# CURRENT_SOURCE.net
KiCad netlist of a schematic drawn in Altium Designer
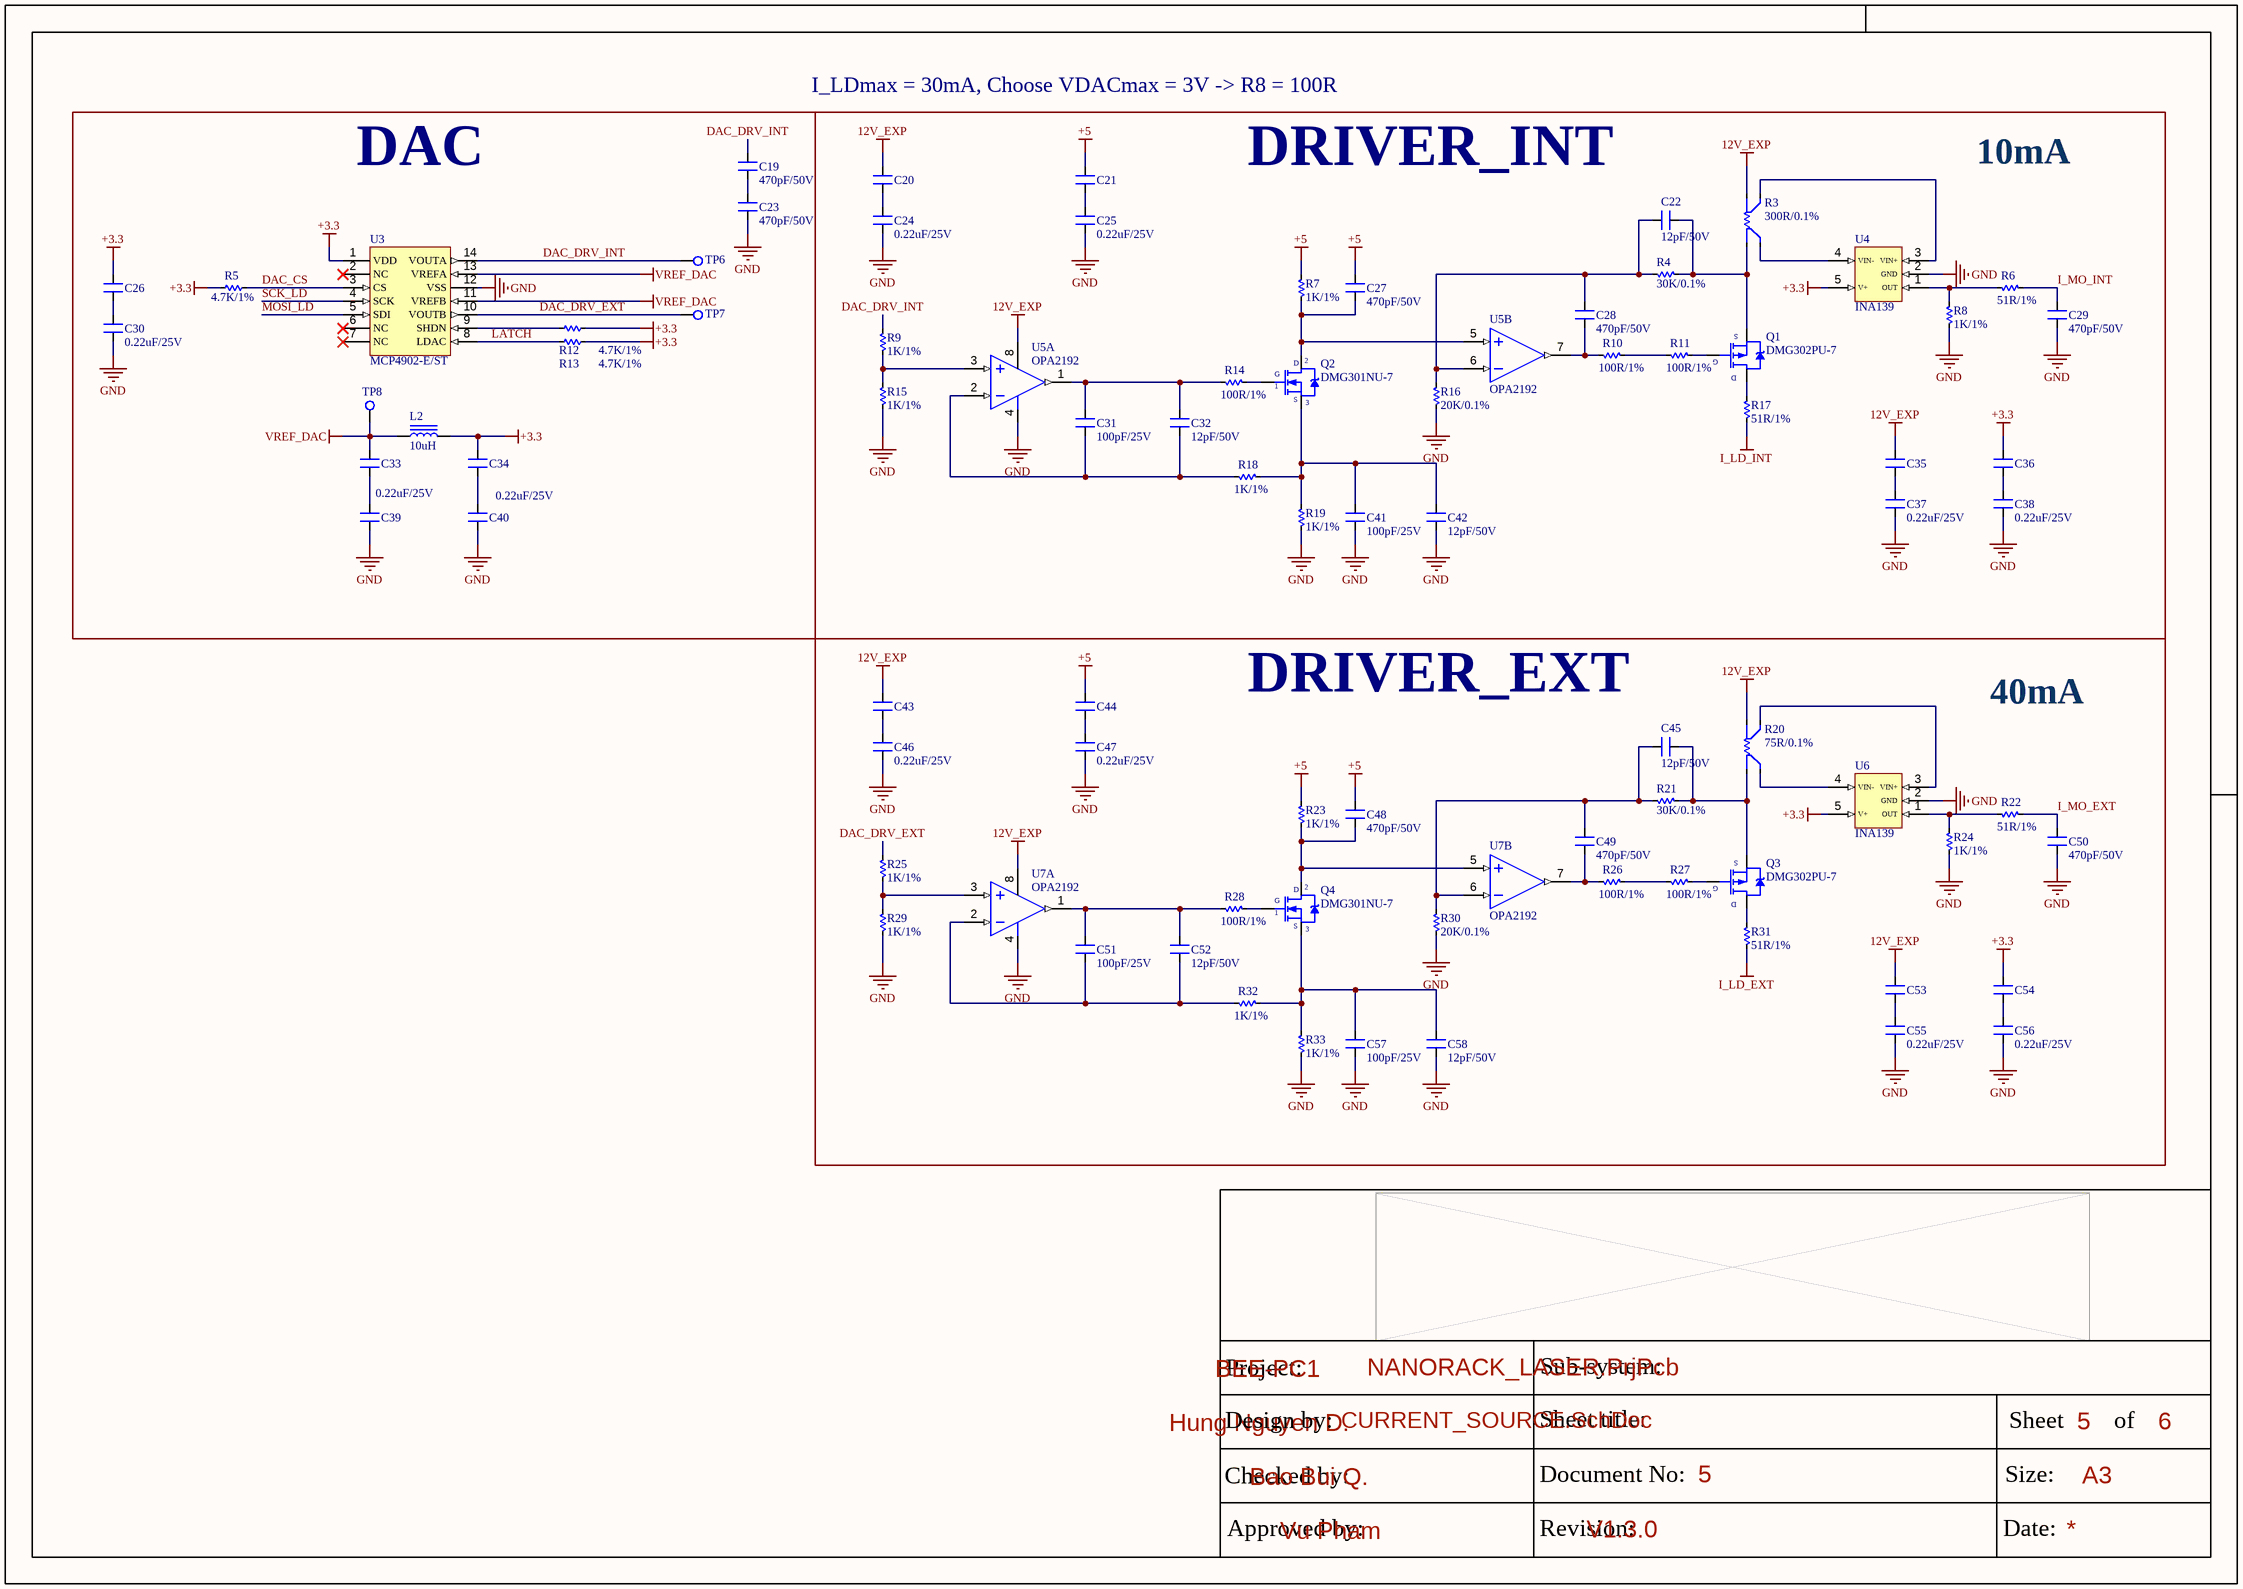
[diagram p0: CURRENT_SOURCE.SchDoc]

(export (version "E")
  (design (tool "Eeschema 10.0.6"))
  (components
    (comp (ref "C19")
      (value "470pF/50V")
      (footprint "SM-0603")
      (description "CL10B471KB8NNNC")
      (libsource (lib "Capacitors") (part "CM"))
    )
    (comp (ref "C20")
      (value "0.22uF/25V")
      (footprint "SM-0603")
      (description "CL10B224KA8NNNC")
      (libsource (lib "Capacitors") (part "CM"))
    )
    (comp (ref "C21")
      (value "0.22uF/25V")
      (footprint "SM-0603")
      (description "CL10B224KA8NNNC")
      (libsource (lib "Capacitors") (part "CM"))
    )
    (comp (ref "C22")
      (value "12pF/50V")
      (footprint "SM-0603")
      (description "CL10C120JB81PNC")
      (libsource (lib "Capacitors") (part "CM"))
    )
    (comp (ref "C23")
      (value "470pF/50V")
      (footprint "SM-0603")
      (description "CL10B471KB8NNNC")
      (libsource (lib "Capacitors") (part "CM"))
    )
    (comp (ref "C24")
      (value "0.22uF/25V")
      (footprint "SM-0603")
      (description "CL10B224KA8NNNC")
      (libsource (lib "Capacitors") (part "CM"))
    )
    (comp (ref "C25")
      (value "0.22uF/25V")
      (footprint "SM-0603")
      (description "CL10B224KA8NNNC")
      (libsource (lib "Capacitors") (part "CM"))
    )
    (comp (ref "C26")
      (value "0.22uF/25V")
      (footprint "SM-0603")
      (description "CL10B224KA8NNNC")
      (libsource (lib "Capacitors") (part "CM"))
    )
    (comp (ref "C27")
      (value "470pF/50V")
      (footprint "SM-0603")
      (description "CL10B471KB8NNNC")
      (libsource (lib "Capacitors") (part "CM"))
    )
    (comp (ref "C28")
      (value "470pF/50V")
      (footprint "SM-0603")
      (description "CL10B471KB8NNNC")
      (libsource (lib "Capacitors") (part "CM"))
    )
    (comp (ref "C29")
      (value "470pF/50V")
      (footprint "SM-0603")
      (description "CL10B471KB8NNNC")
      (libsource (lib "Capacitors") (part "CM"))
    )
    (comp (ref "C30")
      (value "0.22uF/25V")
      (footprint "SM-0603")
      (description "CL10B224KA8NNNC")
      (libsource (lib "Capacitors") (part "CM"))
    )
    (comp (ref "C31")
      (value "100pF/25V")
      (footprint "SM-0603")
      (description "C0603C101M3HACTU")
      (libsource (lib "Capacitors") (part "CM"))
    )
    (comp (ref "C32")
      (value "12pF/50V")
      (footprint "SM-0603")
      (description "CL10C120JB81PNC")
      (libsource (lib "Capacitors") (part "CM"))
    )
    (comp (ref "C33")
      (value "0.22uF/25V")
      (footprint "SM-0603")
      (description "CL10B224KA8NNNC")
      (libsource (lib "Capacitors") (part "CM"))
    )
    (comp (ref "C34")
      (value "0.22uF/25V")
      (footprint "SM-0603")
      (description "CL10B224KA8NNNC")
      (libsource (lib "Capacitors") (part "CM"))
    )
    (comp (ref "C35")
      (value "0.22uF/25V")
      (footprint "SM-0603")
      (description "CL10B224KA8NNNC")
      (libsource (lib "Capacitors") (part "CM"))
    )
    (comp (ref "C36")
      (value "0.22uF/25V")
      (footprint "SM-0603")
      (description "CL10B224KA8NNNC")
      (libsource (lib "Capacitors") (part "CM"))
    )
    (comp (ref "C37")
      (value "0.22uF/25V")
      (footprint "SM-0603")
      (description "CL10B224KA8NNNC")
      (libsource (lib "Capacitors") (part "CM"))
    )
    (comp (ref "C38")
      (value "0.22uF/25V")
      (footprint "SM-0603")
      (description "CL10B224KA8NNNC")
      (libsource (lib "Capacitors") (part "CM"))
    )
    (comp (ref "C39")
      (value "0.22uF/25V")
      (footprint "SM-0603")
      (description "CL10B224KA8NNNC")
      (libsource (lib "Capacitors") (part "CM"))
    )
    (comp (ref "C40")
      (value "0.22uF/25V")
      (footprint "SM-0603")
      (description "CL10B224KA8NNNC")
      (libsource (lib "Capacitors") (part "CM"))
    )
    (comp (ref "C41")
      (value "100pF/25V")
      (footprint "SM-0603")
      (description "C0603C101M3HACTU")
      (libsource (lib "Capacitors") (part "CM"))
    )
    (comp (ref "C42")
      (value "12pF/50V")
      (footprint "SM-0603")
      (description "CL10C120JB81PNC")
      (libsource (lib "Capacitors") (part "CM"))
    )
    (comp (ref "C43")
      (value "0.22uF/25V")
      (footprint "SM-0603")
      (description "CL10B224KA8NNNC")
      (libsource (lib "Capacitors") (part "CM"))
    )
    (comp (ref "C44")
      (value "0.22uF/25V")
      (footprint "SM-0603")
      (description "CL10B224KA8NNNC")
      (libsource (lib "Capacitors") (part "CM"))
    )
    (comp (ref "C45")
      (value "12pF/50V")
      (footprint "SM-0603")
      (description "CL10C120JB81PNC")
      (libsource (lib "Capacitors") (part "CM"))
    )
    (comp (ref "C46")
      (value "0.22uF/25V")
      (footprint "SM-0603")
      (description "CL10B224KA8NNNC")
      (libsource (lib "Capacitors") (part "CM"))
    )
    (comp (ref "C47")
      (value "0.22uF/25V")
      (footprint "SM-0603")
      (description "CL10B224KA8NNNC")
      (libsource (lib "Capacitors") (part "CM"))
    )
    (comp (ref "C48")
      (value "470pF/50V")
      (footprint "SM-0603")
      (description "CL10B471KB8NNNC")
      (libsource (lib "Capacitors") (part "CM"))
    )
    (comp (ref "C49")
      (value "470pF/50V")
      (footprint "SM-0603")
      (description "CL10B471KB8NNNC")
      (libsource (lib "Capacitors") (part "CM"))
    )
    (comp (ref "C50")
      (value "470pF/50V")
      (footprint "SM-0603")
      (description "CL10B471KB8NNNC")
      (libsource (lib "Capacitors") (part "CM"))
    )
    (comp (ref "C51")
      (value "100pF/25V")
      (footprint "SM-0603")
      (description "C0603C101M3HACTU")
      (libsource (lib "Capacitors") (part "CM"))
    )
    (comp (ref "C52")
      (value "12pF/50V")
      (footprint "SM-0603")
      (description "CL10C120JB81PNC")
      (libsource (lib "Capacitors") (part "CM"))
    )
    (comp (ref "C53")
      (value "0.22uF/25V")
      (footprint "SM-0603")
      (description "CL10B224KA8NNNC")
      (libsource (lib "Capacitors") (part "CM"))
    )
    (comp (ref "C54")
      (value "0.22uF/25V")
      (footprint "SM-0603")
      (description "CL10B224KA8NNNC")
      (libsource (lib "Capacitors") (part "CM"))
    )
    (comp (ref "C55")
      (value "0.22uF/25V")
      (footprint "SM-0603")
      (description "CL10B224KA8NNNC")
      (libsource (lib "Capacitors") (part "CM"))
    )
    (comp (ref "C56")
      (value "0.22uF/25V")
      (footprint "SM-0603")
      (description "CL10B224KA8NNNC")
      (libsource (lib "Capacitors") (part "CM"))
    )
    (comp (ref "C57")
      (value "100pF/25V")
      (footprint "SM-0603")
      (description "C0603C101M3HACTU")
      (libsource (lib "Capacitors") (part "CM"))
    )
    (comp (ref "C58")
      (value "12pF/50V")
      (footprint "SM-0603")
      (description "CL10C120JB81PNC")
      (libsource (lib "Capacitors") (part "CM"))
    )
    (comp (ref "L2")
      (value "10uH")
      (footprint "FER 0805/2012")
      (description "MLZ1608N100LT000")
      (libsource (lib "INDUCTOR") (part "Inductor"))
    )
    (comp (ref "Q1")
      (value "DMG302PU-7")
      (footprint "SOT23-3-132")
      (libsource (lib "DAK_Altium_Integrated_Lib") (part "P_MOSFET"))
    )
    (comp (ref "Q2")
      (value "DMG301NU-7")
      (footprint "SOT23-3-132")
      (libsource (lib "DAK_Altium_Integrated_Lib") (part "N_MOSFET"))
    )
    (comp (ref "Q3")
      (value "DMG302PU-7")
      (footprint "SOT23-3-132")
      (libsource (lib "DAK_Altium_Integrated_Lib") (part "P_MOSFET"))
    )
    (comp (ref "Q4")
      (value "DMG301NU-7")
      (footprint "SOT23-3-132")
      (libsource (lib "DAK_Altium_Integrated_Lib") (part "N_MOSFET"))
    )
    (comp (ref "R3")
      (value "300R/0.1%")
      (footprint "RES_SMD_0603_SHUNT")
      (description "RT0603BRC07300RL")
      (libsource (lib "DAK_Altium_Integrated_Lib") (part "RES_SMD_SHUNT"))
    )
    (comp (ref "R4")
      (value "30K/0.1%")
      (footprint "RES-SMD-0603")
      (description "ERA-3AEB303V")
      (fields
        (field (name "MANUFACTURER") "Generic Components")
        (field (name "PUBLISHER") "Altium Hobart Technology Centre")
      )
      (libsource (lib "Library") (part "Res-SMD"))
    )
    (comp (ref "R5")
      (value "4.7K/1%")
      (footprint "RES-SMD-0603")
      (description "ERJ-3EKF4701V")
      (fields
        (field (name "MANUFACTURER") "Generic Components")
        (field (name "PUBLISHER") "Altium Hobart Technology Centre")
      )
      (libsource (lib "Library") (part "Res-SMD"))
    )
    (comp (ref "R6")
      (value "51R/1%")
      (footprint "RES-SMD-0603")
      (description "ERJ-3EKF51R0V")
      (fields
        (field (name "MANUFACTURER") "Generic Components")
        (field (name "PUBLISHER") "Altium Hobart Technology Centre")
      )
      (libsource (lib "Library") (part "Res-SMD"))
    )
    (comp (ref "R7")
      (value "1K/1%")
      (footprint "RES-SMD-0603")
      (description "ERJ-3EKF1001V")
      (fields
        (field (name "MANUFACTURER") "Generic Components")
        (field (name "PUBLISHER") "Altium Hobart Technology Centre")
      )
      (libsource (lib "Library") (part "Res-SMD"))
    )
    (comp (ref "R8")
      (value "1K/1%")
      (footprint "RES-SMD-0603")
      (description "ERJ-3EKF1001V")
      (fields
        (field (name "MANUFACTURER") "Generic Components")
        (field (name "PUBLISHER") "Altium Hobart Technology Centre")
      )
      (libsource (lib "Library") (part "Res-SMD"))
    )
    (comp (ref "R9")
      (value "1K/1%")
      (footprint "RES-SMD-0603")
      (description "ERJ-3EKF1001V")
      (fields
        (field (name "MANUFACTURER") "Generic Components")
        (field (name "PUBLISHER") "Altium Hobart Technology Centre")
      )
      (libsource (lib "Library") (part "Res-SMD"))
    )
    (comp (ref "R10")
      (value "100R/1%")
      (footprint "RES-SMD-0603")
      (description "ERJ-PA3D1000V")
      (fields
        (field (name "MANUFACTURER") "Generic Components")
        (field (name "PUBLISHER") "Altium Hobart Technology Centre")
      )
      (libsource (lib "Library") (part "Res-SMD"))
    )
    (comp (ref "R11")
      (value "100R/1%")
      (footprint "RES-SMD-0603")
      (description "ERJ-PA3D1000V")
      (fields
        (field (name "MANUFACTURER") "Generic Components")
        (field (name "PUBLISHER") "Altium Hobart Technology Centre")
      )
      (libsource (lib "Library") (part "Res-SMD"))
    )
    (comp (ref "R12")
      (value "4.7K/1%")
      (footprint "RES-SMD-0603")
      (description "ERJ-3EKF4701V")
      (fields
        (field (name "MANUFACTURER") "Generic Components")
        (field (name "PUBLISHER") "Altium Hobart Technology Centre")
      )
      (libsource (lib "Library") (part "Res-SMD"))
    )
    (comp (ref "R13")
      (value "4.7K/1%")
      (footprint "RES-SMD-0603")
      (description "ERJ-3EKF4701V")
      (fields
        (field (name "MANUFACTURER") "Generic Components")
        (field (name "PUBLISHER") "Altium Hobart Technology Centre")
      )
      (libsource (lib "Library") (part "Res-SMD"))
    )
    (comp (ref "R14")
      (value "100R/1%")
      (footprint "RES-SMD-0603")
      (description "ERJ-PA3D1000V")
      (fields
        (field (name "MANUFACTURER") "Generic Components")
        (field (name "PUBLISHER") "Altium Hobart Technology Centre")
      )
      (libsource (lib "Library") (part "Res-SMD"))
    )
    (comp (ref "R15")
      (value "1K/1%")
      (footprint "RES-SMD-0603")
      (description "ERJ-3EKF1001V")
      (fields
        (field (name "MANUFACTURER") "Generic Components")
        (field (name "PUBLISHER") "Altium Hobart Technology Centre")
      )
      (libsource (lib "Library") (part "Res-SMD"))
    )
    (comp (ref "R16")
      (value "20K/0.1%")
      (footprint "RES-SMD-0603")
      (description "ERA-3AEB203V")
      (fields
        (field (name "MANUFACTURER") "Generic Components")
        (field (name "PUBLISHER") "Altium Hobart Technology Centre")
      )
      (libsource (lib "Library") (part "Res-SMD"))
    )
    (comp (ref "R17")
      (value "51R/1%")
      (footprint "RES-SMD-0603")
      (description "ERJ-3EKF51R0V")
      (fields
        (field (name "MANUFACTURER") "Generic Components")
        (field (name "PUBLISHER") "Altium Hobart Technology Centre")
      )
      (libsource (lib "Library") (part "Res-SMD"))
    )
    (comp (ref "R18")
      (value "1K/1%")
      (footprint "RES-SMD-0603")
      (description "ERJ-3EKF1001V")
      (fields
        (field (name "MANUFACTURER") "Generic Components")
        (field (name "PUBLISHER") "Altium Hobart Technology Centre")
      )
      (libsource (lib "Library") (part "Res-SMD"))
    )
    (comp (ref "R19")
      (value "1K/1%")
      (footprint "RES-SMD-0603")
      (description "ERJ-3EKF1001V")
      (fields
        (field (name "MANUFACTURER") "Generic Components")
        (field (name "PUBLISHER") "Altium Hobart Technology Centre")
      )
      (libsource (lib "Library") (part "Res-SMD"))
    )
    (comp (ref "R20")
      (value "75R/0.1%")
      (footprint "RES_SMD_0603_SHUNT")
      (description "TNPW060375R0BEEA")
      (libsource (lib "DAK_Altium_Integrated_Lib") (part "RES_SMD_SHUNT"))
    )
    (comp (ref "R21")
      (value "30K/0.1%")
      (footprint "RES-SMD-0603")
      (description "ERA-3AEB303V")
      (fields
        (field (name "MANUFACTURER") "Generic Components")
        (field (name "PUBLISHER") "Altium Hobart Technology Centre")
      )
      (libsource (lib "Library") (part "Res-SMD"))
    )
    (comp (ref "R22")
      (value "51R/1%")
      (footprint "RES-SMD-0603")
      (description "ERJ-3EKF51R0V")
      (fields
        (field (name "MANUFACTURER") "Generic Components")
        (field (name "PUBLISHER") "Altium Hobart Technology Centre")
      )
      (libsource (lib "Library") (part "Res-SMD"))
    )
    (comp (ref "R23")
      (value "1K/1%")
      (footprint "RES-SMD-0603")
      (description "ERJ-3EKF1001V")
      (fields
        (field (name "MANUFACTURER") "Generic Components")
        (field (name "PUBLISHER") "Altium Hobart Technology Centre")
      )
      (libsource (lib "Library") (part "Res-SMD"))
    )
    (comp (ref "R24")
      (value "1K/1%")
      (footprint "RES-SMD-0603")
      (description "ERJ-3EKF1001V")
      (fields
        (field (name "MANUFACTURER") "Generic Components")
        (field (name "PUBLISHER") "Altium Hobart Technology Centre")
      )
      (libsource (lib "Library") (part "Res-SMD"))
    )
    (comp (ref "R25")
      (value "1K/1%")
      (footprint "RES-SMD-0603")
      (description "ERJ-3EKF1001V")
      (fields
        (field (name "MANUFACTURER") "Generic Components")
        (field (name "PUBLISHER") "Altium Hobart Technology Centre")
      )
      (libsource (lib "Library") (part "Res-SMD"))
    )
    (comp (ref "R26")
      (value "100R/1%")
      (footprint "RES-SMD-0603")
      (description "ERJ-PA3D1000V")
      (fields
        (field (name "MANUFACTURER") "Generic Components")
        (field (name "PUBLISHER") "Altium Hobart Technology Centre")
      )
      (libsource (lib "Library") (part "Res-SMD"))
    )
    (comp (ref "R27")
      (value "100R/1%")
      (footprint "RES-SMD-0603")
      (description "ERJ-PA3D1000V")
      (fields
        (field (name "MANUFACTURER") "Generic Components")
        (field (name "PUBLISHER") "Altium Hobart Technology Centre")
      )
      (libsource (lib "Library") (part "Res-SMD"))
    )
    (comp (ref "R28")
      (value "100R/1%")
      (footprint "RES-SMD-0603")
      (description "ERJ-PA3D1000V")
      (fields
        (field (name "MANUFACTURER") "Generic Components")
        (field (name "PUBLISHER") "Altium Hobart Technology Centre")
      )
      (libsource (lib "Library") (part "Res-SMD"))
    )
    (comp (ref "R29")
      (value "1K/1%")
      (footprint "RES-SMD-0603")
      (description "ERJ-3EKF1001V")
      (fields
        (field (name "MANUFACTURER") "Generic Components")
        (field (name "PUBLISHER") "Altium Hobart Technology Centre")
      )
      (libsource (lib "Library") (part "Res-SMD"))
    )
    (comp (ref "R30")
      (value "20K/0.1%")
      (footprint "RES-SMD-0603")
      (description "ERA-3AEB203V")
      (fields
        (field (name "MANUFACTURER") "Generic Components")
        (field (name "PUBLISHER") "Altium Hobart Technology Centre")
      )
      (libsource (lib "Library") (part "Res-SMD"))
    )
    (comp (ref "R31")
      (value "51R/1%")
      (footprint "RES-SMD-0603")
      (description "ERJ-3EKF51R0V")
      (fields
        (field (name "MANUFACTURER") "Generic Components")
        (field (name "PUBLISHER") "Altium Hobart Technology Centre")
      )
      (libsource (lib "Library") (part "Res-SMD"))
    )
    (comp (ref "R32")
      (value "1K/1%")
      (footprint "RES-SMD-0603")
      (description "ERJ-3EKF1001V")
      (fields
        (field (name "MANUFACTURER") "Generic Components")
        (field (name "PUBLISHER") "Altium Hobart Technology Centre")
      )
      (libsource (lib "Library") (part "Res-SMD"))
    )
    (comp (ref "R33")
      (value "1K/1%")
      (footprint "RES-SMD-0603")
      (description "ERJ-3EKF1001V")
      (fields
        (field (name "MANUFACTURER") "Generic Components")
        (field (name "PUBLISHER") "Altium Hobart Technology Centre")
      )
      (libsource (lib "Library") (part "Res-SMD"))
    )
    (comp (ref "TP6")
      (value "Test_Point")
      (footprint "TESTPOINT")
      (libsource (lib "Library_HUNG") (part "Test_Point"))
    )
    (comp (ref "TP7")
      (value "Test_Point")
      (footprint "TESTPOINT")
      (libsource (lib "Library_HUNG") (part "Test_Point"))
    )
    (comp (ref "TP8")
      (value "Test_Point")
      (footprint "TESTPOINT")
      (libsource (lib "Library_HUNG") (part "Test_Point"))
    )
    (comp (ref "U3")
      (value "MCP4902-E/ST")
      (footprint "TSSOP14")
      (libsource (lib "Library") (part "MCP4902"))
    )
    (comp (ref "U4")
      (value "INA139")
      (footprint "SOT23-5")
      (description "INA139NA/250")
      (libsource (lib "Library_HUNG") (part "INA139"))
    )
    (comp (ref "U5")
      (value "OPA2192")
      (footprint "SO8")
      (description "OPA2192IDR")
      (libsource (lib "Library") (part "LM358"))
    )
    (comp (ref "U6")
      (value "INA139")
      (footprint "SOT23-5")
      (description "INA139NA/250")
      (libsource (lib "Library_HUNG") (part "INA139"))
    )
    (comp (ref "U7")
      (value "OPA2192")
      (footprint "SO8")
      (description "OPA2192IDR")
      (libsource (lib "Library") (part "LM358"))
    )
  )
  (nets
    (net (code "1") (name "+3.3") (class "Default")
      (node (ref "C26") (pin "2") (pinfunction "2_2") (pintype "passive"))
      (node (ref "C34") (pin "2") (pinfunction "2_2") (pintype "passive"))
      (node (ref "C36") (pin "2") (pinfunction "2_2") (pintype "passive"))
      (node (ref "C54") (pin "2") (pinfunction "2_2") (pintype "passive"))
      (node (ref "L2") (pin "2") (pinfunction "2_2") (pintype "passive"))
      (node (ref "R12") (pin "1") (pinfunction "1_1") (pintype "passive"))
      (node (ref "R13") (pin "1") (pinfunction "1_1") (pintype "passive"))
      (node (ref "R5") (pin "2") (pinfunction "2_2") (pintype "passive"))
      (node (ref "U3") (pin "1") (pinfunction "VDD_1") (pintype "power_in"))
      (node (ref "U4") (pin "5") (pinfunction "V+_5") (pintype "input"))
      (node (ref "U6") (pin "5") (pinfunction "V+_5") (pintype "input"))
    )
    (net (code "2") (name "+5") (class "Default")
      (node (ref "C21") (pin "2") (pinfunction "2_2") (pintype "passive"))
      (node (ref "C27") (pin "2") (pinfunction "2_2") (pintype "passive"))
      (node (ref "C44") (pin "2") (pinfunction "2_2") (pintype "passive"))
      (node (ref "C48") (pin "2") (pinfunction "2_2") (pintype "passive"))
      (node (ref "R23") (pin "2") (pinfunction "2_2") (pintype "passive"))
      (node (ref "R7") (pin "2") (pinfunction "2_2") (pintype "passive"))
    )
    (net (code "3") (name "/DAC_CS") (class "Default")
      (node (ref "R5") (pin "1") (pinfunction "1_1") (pintype "passive"))
      (node (ref "U3") (pin "3") (pinfunction "CS_3") (pintype "input"))
    )
    (net (code "4") (name "/DAC_DRV_EXT") (class "Default")
      (node (ref "R25") (pin "2") (pinfunction "2_2") (pintype "passive"))
      (node (ref "TP7") (pin "1") (pintype "power_in"))
      (node (ref "U3") (pin "10") (pinfunction "VOUTB_10") (pintype "output"))
    )
    (net (code "5") (name "/DAC_DRV_INT") (class "Default")
      (node (ref "C19") (pin "2") (pinfunction "2_2") (pintype "passive"))
      (node (ref "R9") (pin "2") (pinfunction "2_2") (pintype "passive"))
      (node (ref "TP6") (pin "1") (pintype "power_in"))
      (node (ref "U3") (pin "14") (pinfunction "VOUTA_14") (pintype "output"))
    )
    (net (code "6") (name "/I_MO_EXT") (class "Default")
      (node (ref "C50") (pin "2") (pinfunction "2_2") (pintype "passive"))
      (node (ref "R22") (pin "2") (pinfunction "2_2") (pintype "passive"))
    )
    (net (code "7") (name "/I_MO_INT") (class "Default")
      (node (ref "C29") (pin "2") (pinfunction "2_2") (pintype "passive"))
      (node (ref "R6") (pin "2") (pinfunction "2_2") (pintype "passive"))
    )
    (net (code "8") (name "/LATCH") (class "Default")
      (node (ref "R13") (pin "2") (pinfunction "2_2") (pintype "passive"))
      (node (ref "U3") (pin "8") (pinfunction "LDAC_8") (pintype "input"))
    )
    (net (code "9") (name "/MOSI_LD") (class "Default")
      (node (ref "U3") (pin "5") (pinfunction "SDI_5") (pintype "input"))
    )
    (net (code "10") (name "/SCK_LD") (class "Default")
      (node (ref "U3") (pin "4") (pinfunction "SCK_4") (pintype "input"))
    )
    (net (code "11") (name "12V_EXP") (class "Default")
      (node (ref "C20") (pin "2") (pinfunction "2_2") (pintype "passive"))
      (node (ref "C35") (pin "2") (pinfunction "2_2") (pintype "passive"))
      (node (ref "C43") (pin "2") (pinfunction "2_2") (pintype "passive"))
      (node (ref "C53") (pin "2") (pinfunction "2_2") (pintype "passive"))
      (node (ref "R20") (pin "1") (pinfunction "1_1") (pintype "passive"))
      (node (ref "R3") (pin "1") (pinfunction "1_1") (pintype "passive"))
      (node (ref "U5") (pin "8") (pinfunction "+V_8") (pintype "passive"))
      (node (ref "U7") (pin "8") (pinfunction "+V_8") (pintype "passive"))
    )
    (net (code "12") (name "GND") (class "Default")
      (node (ref "C23") (pin "1") (pinfunction "1_1") (pintype "passive"))
      (node (ref "C24") (pin "1") (pinfunction "1_1") (pintype "passive"))
      (node (ref "C25") (pin "1") (pinfunction "1_1") (pintype "passive"))
      (node (ref "C29") (pin "1") (pinfunction "1_1") (pintype "passive"))
      (node (ref "C30") (pin "1") (pinfunction "1_1") (pintype "passive"))
      (node (ref "C37") (pin "1") (pinfunction "1_1") (pintype "passive"))
      (node (ref "C38") (pin "1") (pinfunction "1_1") (pintype "passive"))
      (node (ref "C39") (pin "1") (pinfunction "1_1") (pintype "passive"))
      (node (ref "C40") (pin "1") (pinfunction "1_1") (pintype "passive"))
      (node (ref "C41") (pin "1") (pinfunction "1_1") (pintype "passive"))
      (node (ref "C42") (pin "2") (pinfunction "2_2") (pintype "passive"))
      (node (ref "C46") (pin "1") (pinfunction "1_1") (pintype "passive"))
      (node (ref "C47") (pin "1") (pinfunction "1_1") (pintype "passive"))
      (node (ref "C50") (pin "1") (pinfunction "1_1") (pintype "passive"))
      (node (ref "C55") (pin "1") (pinfunction "1_1") (pintype "passive"))
      (node (ref "C56") (pin "1") (pinfunction "1_1") (pintype "passive"))
      (node (ref "C57") (pin "1") (pinfunction "1_1") (pintype "passive"))
      (node (ref "C58") (pin "2") (pinfunction "2_2") (pintype "passive"))
      (node (ref "R15") (pin "1") (pinfunction "1_1") (pintype "passive"))
      (node (ref "R16") (pin "1") (pinfunction "1_1") (pintype "passive"))
      (node (ref "R19") (pin "1") (pinfunction "1_1") (pintype "passive"))
      (node (ref "R24") (pin "2") (pinfunction "2_2") (pintype "passive"))
      (node (ref "R29") (pin "1") (pinfunction "1_1") (pintype "passive"))
      (node (ref "R30") (pin "1") (pinfunction "1_1") (pintype "passive"))
      (node (ref "R33") (pin "1") (pinfunction "1_1") (pintype "passive"))
      (node (ref "R8") (pin "2") (pinfunction "2_2") (pintype "passive"))
      (node (ref "U3") (pin "12") (pinfunction "VSS_12") (pintype "power_in"))
      (node (ref "U4") (pin "2") (pinfunction "GND_2") (pintype "input"))
      (node (ref "U5") (pin "4") (pinfunction "-V_4") (pintype "passive"))
      (node (ref "U6") (pin "2") (pinfunction "GND_2") (pintype "input"))
      (node (ref "U7") (pin "4") (pinfunction "-V_4") (pintype "passive"))
    )
    (net (code "13") (name "I_LD_EXT") (class "Default")
      (node (ref "R31") (pin "1") (pinfunction "1_1") (pintype "passive"))
    )
    (net (code "14") (name "I_LD_INT") (class "Default")
      (node (ref "R17") (pin "1") (pinfunction "1_1") (pintype "passive"))
    )
    (net (code "15") (name "Net-(C19-Pad1)") (class "Default")
      (node (ref "C19") (pin "1") (pinfunction "1_1") (pintype "passive"))
      (node (ref "C23") (pin "2") (pinfunction "2_2") (pintype "passive"))
    )
    (net (code "16") (name "Net-(C20-Pad1)") (class "Default")
      (node (ref "C20") (pin "1") (pinfunction "1_1") (pintype "passive"))
      (node (ref "C24") (pin "2") (pinfunction "2_2") (pintype "passive"))
    )
    (net (code "17") (name "Net-(C21-Pad1)") (class "Default")
      (node (ref "C21") (pin "1") (pinfunction "1_1") (pintype "passive"))
      (node (ref "C25") (pin "2") (pinfunction "2_2") (pintype "passive"))
    )
    (net (code "18") (name "Net-(C26-Pad1)") (class "Default")
      (node (ref "C26") (pin "1") (pinfunction "1_1") (pintype "passive"))
      (node (ref "C30") (pin "2") (pinfunction "2_2") (pintype "passive"))
    )
    (net (code "19") (name "Net-(C33-Pad1)") (class "Default")
      (node (ref "C33") (pin "1") (pinfunction "1_1") (pintype "passive"))
      (node (ref "C39") (pin "2") (pinfunction "2_2") (pintype "passive"))
    )
    (net (code "20") (name "Net-(C34-Pad1)") (class "Default")
      (node (ref "C34") (pin "1") (pinfunction "1_1") (pintype "passive"))
      (node (ref "C40") (pin "2") (pinfunction "2_2") (pintype "passive"))
    )
    (net (code "21") (name "Net-(C35-Pad1)") (class "Default")
      (node (ref "C35") (pin "1") (pinfunction "1_1") (pintype "passive"))
      (node (ref "C37") (pin "2") (pinfunction "2_2") (pintype "passive"))
    )
    (net (code "22") (name "Net-(C36-Pad1)") (class "Default")
      (node (ref "C36") (pin "1") (pinfunction "1_1") (pintype "passive"))
      (node (ref "C38") (pin "2") (pinfunction "2_2") (pintype "passive"))
    )
    (net (code "23") (name "Net-(C43-Pad1)") (class "Default")
      (node (ref "C43") (pin "1") (pinfunction "1_1") (pintype "passive"))
      (node (ref "C46") (pin "2") (pinfunction "2_2") (pintype "passive"))
    )
    (net (code "24") (name "Net-(C44-Pad1)") (class "Default")
      (node (ref "C44") (pin "1") (pinfunction "1_1") (pintype "passive"))
      (node (ref "C47") (pin "2") (pinfunction "2_2") (pintype "passive"))
    )
    (net (code "25") (name "Net-(C53-Pad1)") (class "Default")
      (node (ref "C53") (pin "1") (pinfunction "1_1") (pintype "passive"))
      (node (ref "C55") (pin "2") (pinfunction "2_2") (pintype "passive"))
    )
    (net (code "26") (name "Net-(C54-Pad1)") (class "Default")
      (node (ref "C54") (pin "1") (pinfunction "1_1") (pintype "passive"))
      (node (ref "C56") (pin "2") (pinfunction "2_2") (pintype "passive"))
    )
    (net (code "27") (name "Net-(Q1-D)") (class "Default")
      (node (ref "Q1") (pin "2") (pinfunction "D_2") (pintype "passive"))
      (node (ref "R17") (pin "2") (pinfunction "2_2") (pintype "passive"))
    )
    (net (code "28") (name "Net-(Q1-G)") (class "Default")
      (node (ref "Q1") (pin "1") (pinfunction "G_1") (pintype "passive"))
      (node (ref "R11") (pin "2") (pinfunction "2_2") (pintype "passive"))
    )
    (net (code "29") (name "Net-(Q1-S)") (class "Default")
      (node (ref "C22") (pin "1") (pinfunction "1_1") (pintype "passive"))
      (node (ref "Q1") (pin "3") (pinfunction "S_3") (pintype "passive"))
      (node (ref "R3") (pin "2") (pinfunction "2_2") (pintype "passive"))
      (node (ref "R4") (pin "1") (pinfunction "1_1") (pintype "passive"))
    )
    (net (code "30") (name "Net-(Q2-D)") (class "Default")
      (node (ref "C27") (pin "1") (pinfunction "1_1") (pintype "passive"))
      (node (ref "Q2") (pin "2") (pinfunction "D_2") (pintype "passive"))
      (node (ref "R7") (pin "1") (pinfunction "1_1") (pintype "passive"))
      (node (ref "U5") (pin "5") (pinfunction "IN+_5") (pintype "input"))
    )
    (net (code "31") (name "Net-(Q2-G)") (class "Default")
      (node (ref "Q2") (pin "1") (pinfunction "G_1") (pintype "passive"))
      (node (ref "R14") (pin "2") (pinfunction "2_2") (pintype "passive"))
    )
    (net (code "32") (name "Net-(Q2-S)") (class "Default")
      (node (ref "C41") (pin "2") (pinfunction "2_2") (pintype "passive"))
      (node (ref "C42") (pin "1") (pinfunction "1_1") (pintype "passive"))
      (node (ref "Q2") (pin "3") (pinfunction "S_3") (pintype "passive"))
      (node (ref "R18") (pin "2") (pinfunction "2_2") (pintype "passive"))
      (node (ref "R19") (pin "2") (pinfunction "2_2") (pintype "passive"))
    )
    (net (code "33") (name "Net-(Q3-D)") (class "Default")
      (node (ref "Q3") (pin "2") (pinfunction "D_2") (pintype "passive"))
      (node (ref "R31") (pin "2") (pinfunction "2_2") (pintype "passive"))
    )
    (net (code "34") (name "Net-(Q3-G)") (class "Default")
      (node (ref "Q3") (pin "1") (pinfunction "G_1") (pintype "passive"))
      (node (ref "R27") (pin "2") (pinfunction "2_2") (pintype "passive"))
    )
    (net (code "35") (name "Net-(Q3-S)") (class "Default")
      (node (ref "C45") (pin "1") (pinfunction "1_1") (pintype "passive"))
      (node (ref "Q3") (pin "3") (pinfunction "S_3") (pintype "passive"))
      (node (ref "R20") (pin "2") (pinfunction "2_2") (pintype "passive"))
      (node (ref "R21") (pin "1") (pinfunction "1_1") (pintype "passive"))
    )
    (net (code "36") (name "Net-(Q4-D)") (class "Default")
      (node (ref "C48") (pin "1") (pinfunction "1_1") (pintype "passive"))
      (node (ref "Q4") (pin "2") (pinfunction "D_2") (pintype "passive"))
      (node (ref "R23") (pin "1") (pinfunction "1_1") (pintype "passive"))
      (node (ref "U7") (pin "5") (pinfunction "IN+_5") (pintype "input"))
    )
    (net (code "37") (name "Net-(Q4-G)") (class "Default")
      (node (ref "Q4") (pin "1") (pinfunction "G_1") (pintype "passive"))
      (node (ref "R28") (pin "2") (pinfunction "2_2") (pintype "passive"))
    )
    (net (code "38") (name "Net-(Q4-S)") (class "Default")
      (node (ref "C57") (pin "2") (pinfunction "2_2") (pintype "passive"))
      (node (ref "C58") (pin "1") (pinfunction "1_1") (pintype "passive"))
      (node (ref "Q4") (pin "3") (pinfunction "S_3") (pintype "passive"))
      (node (ref "R32") (pin "2") (pinfunction "2_2") (pintype "passive"))
      (node (ref "R33") (pin "2") (pinfunction "2_2") (pintype "passive"))
    )
    (net (code "39") (name "Net-(R10-Pad2)") (class "Default")
      (node (ref "R10") (pin "2") (pinfunction "2_2") (pintype "passive"))
      (node (ref "R11") (pin "1") (pinfunction "1_1") (pintype "passive"))
    )
    (net (code "40") (name "Net-(R26-Pad2)") (class "Default")
      (node (ref "R26") (pin "2") (pinfunction "2_2") (pintype "passive"))
      (node (ref "R27") (pin "1") (pinfunction "1_1") (pintype "passive"))
    )
    (net (code "41") (name "Net-(U3-SHDN)") (class "Default")
      (node (ref "R12") (pin "2") (pinfunction "2_2") (pintype "passive"))
      (node (ref "U3") (pin "9") (pinfunction "SHDN_9") (pintype "input"))
    )
    (net (code "42") (name "Net-(U4-OUT)") (class "Default")
      (node (ref "R6") (pin "1") (pinfunction "1_1") (pintype "passive"))
      (node (ref "R8") (pin "1") (pinfunction "1_1") (pintype "passive"))
      (node (ref "U4") (pin "1") (pinfunction "OUT_1") (pintype "input"))
    )
    (net (code "43") (name "Net-(U4-VIN+)") (class "Default")
      (node (ref "R3") (pin "3") (pinfunction "3_3") (pintype "passive"))
      (node (ref "U4") (pin "3") (pinfunction "VIN+_3") (pintype "input"))
    )
    (net (code "44") (name "Net-(U4-VIN-)") (class "Default")
      (node (ref "R3") (pin "4") (pinfunction "4_4") (pintype "passive"))
      (node (ref "U4") (pin "4") (pinfunction "VIN-_4") (pintype "input"))
    )
    (net (code "45") (name "Net-(U5A-IN+)") (class "Default")
      (node (ref "R15") (pin "2") (pinfunction "2_2") (pintype "passive"))
      (node (ref "R9") (pin "1") (pinfunction "1_1") (pintype "passive"))
      (node (ref "U5") (pin "3") (pinfunction "IN+_3") (pintype "input"))
    )
    (net (code "46") (name "Net-(U5A-IN-)") (class "Default")
      (node (ref "C31") (pin "1") (pinfunction "1_1") (pintype "passive"))
      (node (ref "C32") (pin "1") (pinfunction "1_1") (pintype "passive"))
      (node (ref "R18") (pin "1") (pinfunction "1_1") (pintype "passive"))
      (node (ref "U5") (pin "2") (pinfunction "IN-_2") (pintype "input"))
    )
    (net (code "47") (name "Net-(U5A-OUT)") (class "Default")
      (node (ref "C31") (pin "2") (pinfunction "2_2") (pintype "passive"))
      (node (ref "C32") (pin "2") (pinfunction "2_2") (pintype "passive"))
      (node (ref "R14") (pin "1") (pinfunction "1_1") (pintype "passive"))
      (node (ref "U5") (pin "1") (pinfunction "OUT_1") (pintype "output"))
    )
    (net (code "48") (name "Net-(U5B-IN-)") (class "Default")
      (node (ref "C22") (pin "2") (pinfunction "2_2") (pintype "passive"))
      (node (ref "C28") (pin "2") (pinfunction "2_2") (pintype "passive"))
      (node (ref "R16") (pin "2") (pinfunction "2_2") (pintype "passive"))
      (node (ref "R4") (pin "2") (pinfunction "2_2") (pintype "passive"))
      (node (ref "U5") (pin "6") (pinfunction "IN-_6") (pintype "input"))
    )
    (net (code "49") (name "Net-(U5B-OUT)") (class "Default")
      (node (ref "C28") (pin "1") (pinfunction "1_1") (pintype "passive"))
      (node (ref "R10") (pin "1") (pinfunction "1_1") (pintype "passive"))
      (node (ref "U5") (pin "7") (pinfunction "OUT_7") (pintype "output"))
    )
    (net (code "50") (name "Net-(U6-OUT)") (class "Default")
      (node (ref "R22") (pin "1") (pinfunction "1_1") (pintype "passive"))
      (node (ref "R24") (pin "1") (pinfunction "1_1") (pintype "passive"))
      (node (ref "U6") (pin "1") (pinfunction "OUT_1") (pintype "input"))
    )
    (net (code "51") (name "Net-(U6-VIN+)") (class "Default")
      (node (ref "R20") (pin "3") (pinfunction "3_3") (pintype "passive"))
      (node (ref "U6") (pin "3") (pinfunction "VIN+_3") (pintype "input"))
    )
    (net (code "52") (name "Net-(U6-VIN-)") (class "Default")
      (node (ref "R20") (pin "4") (pinfunction "4_4") (pintype "passive"))
      (node (ref "U6") (pin "4") (pinfunction "VIN-_4") (pintype "input"))
    )
    (net (code "53") (name "Net-(U7A-IN+)") (class "Default")
      (node (ref "R25") (pin "1") (pinfunction "1_1") (pintype "passive"))
      (node (ref "R29") (pin "2") (pinfunction "2_2") (pintype "passive"))
      (node (ref "U7") (pin "3") (pinfunction "IN+_3") (pintype "input"))
    )
    (net (code "54") (name "Net-(U7A-IN-)") (class "Default")
      (node (ref "C51") (pin "1") (pinfunction "1_1") (pintype "passive"))
      (node (ref "C52") (pin "1") (pinfunction "1_1") (pintype "passive"))
      (node (ref "R32") (pin "1") (pinfunction "1_1") (pintype "passive"))
      (node (ref "U7") (pin "2") (pinfunction "IN-_2") (pintype "input"))
    )
    (net (code "55") (name "Net-(U7A-OUT)") (class "Default")
      (node (ref "C51") (pin "2") (pinfunction "2_2") (pintype "passive"))
      (node (ref "C52") (pin "2") (pinfunction "2_2") (pintype "passive"))
      (node (ref "R28") (pin "1") (pinfunction "1_1") (pintype "passive"))
      (node (ref "U7") (pin "1") (pinfunction "OUT_1") (pintype "output"))
    )
    (net (code "56") (name "Net-(U7B-IN-)") (class "Default")
      (node (ref "C45") (pin "2") (pinfunction "2_2") (pintype "passive"))
      (node (ref "C49") (pin "2") (pinfunction "2_2") (pintype "passive"))
      (node (ref "R21") (pin "2") (pinfunction "2_2") (pintype "passive"))
      (node (ref "R30") (pin "2") (pinfunction "2_2") (pintype "passive"))
      (node (ref "U7") (pin "6") (pinfunction "IN-_6") (pintype "input"))
    )
    (net (code "57") (name "Net-(U7B-OUT)") (class "Default")
      (node (ref "C49") (pin "1") (pinfunction "1_1") (pintype "passive"))
      (node (ref "R26") (pin "1") (pinfunction "1_1") (pintype "passive"))
      (node (ref "U7") (pin "7") (pinfunction "OUT_7") (pintype "output"))
    )
    (net (code "58") (name "VREF_DAC") (class "Default")
      (node (ref "C33") (pin "2") (pinfunction "2_2") (pintype "passive"))
      (node (ref "L2") (pin "1") (pinfunction "1_1") (pintype "passive"))
      (node (ref "TP8") (pin "1") (pintype "power_in"))
      (node (ref "U3") (pin "11") (pinfunction "VREFB_11") (pintype "input"))
      (node (ref "U3") (pin "13") (pinfunction "VREFA_13") (pintype "input"))
    )
    (net (code "59") (name "unconnected-(U3-NC-Pad2)") (class "Default")
      (node (ref "U3") (pin "2") (pinfunction "NC_2") (pintype "tri_state+no_connect"))
    )
    (net (code "60") (name "unconnected-(U3-NC-Pad6)") (class "Default")
      (node (ref "U3") (pin "6") (pinfunction "NC_6") (pintype "tri_state+no_connect"))
    )
    (net (code "61") (name "unconnected-(U3-NC-Pad7)") (class "Default")
      (node (ref "U3") (pin "7") (pinfunction "NC_7") (pintype "tri_state+no_connect"))
    )
  )
)
